# 1_PWR.net
KiCad netlist of a schematic drawn in Altium Designer
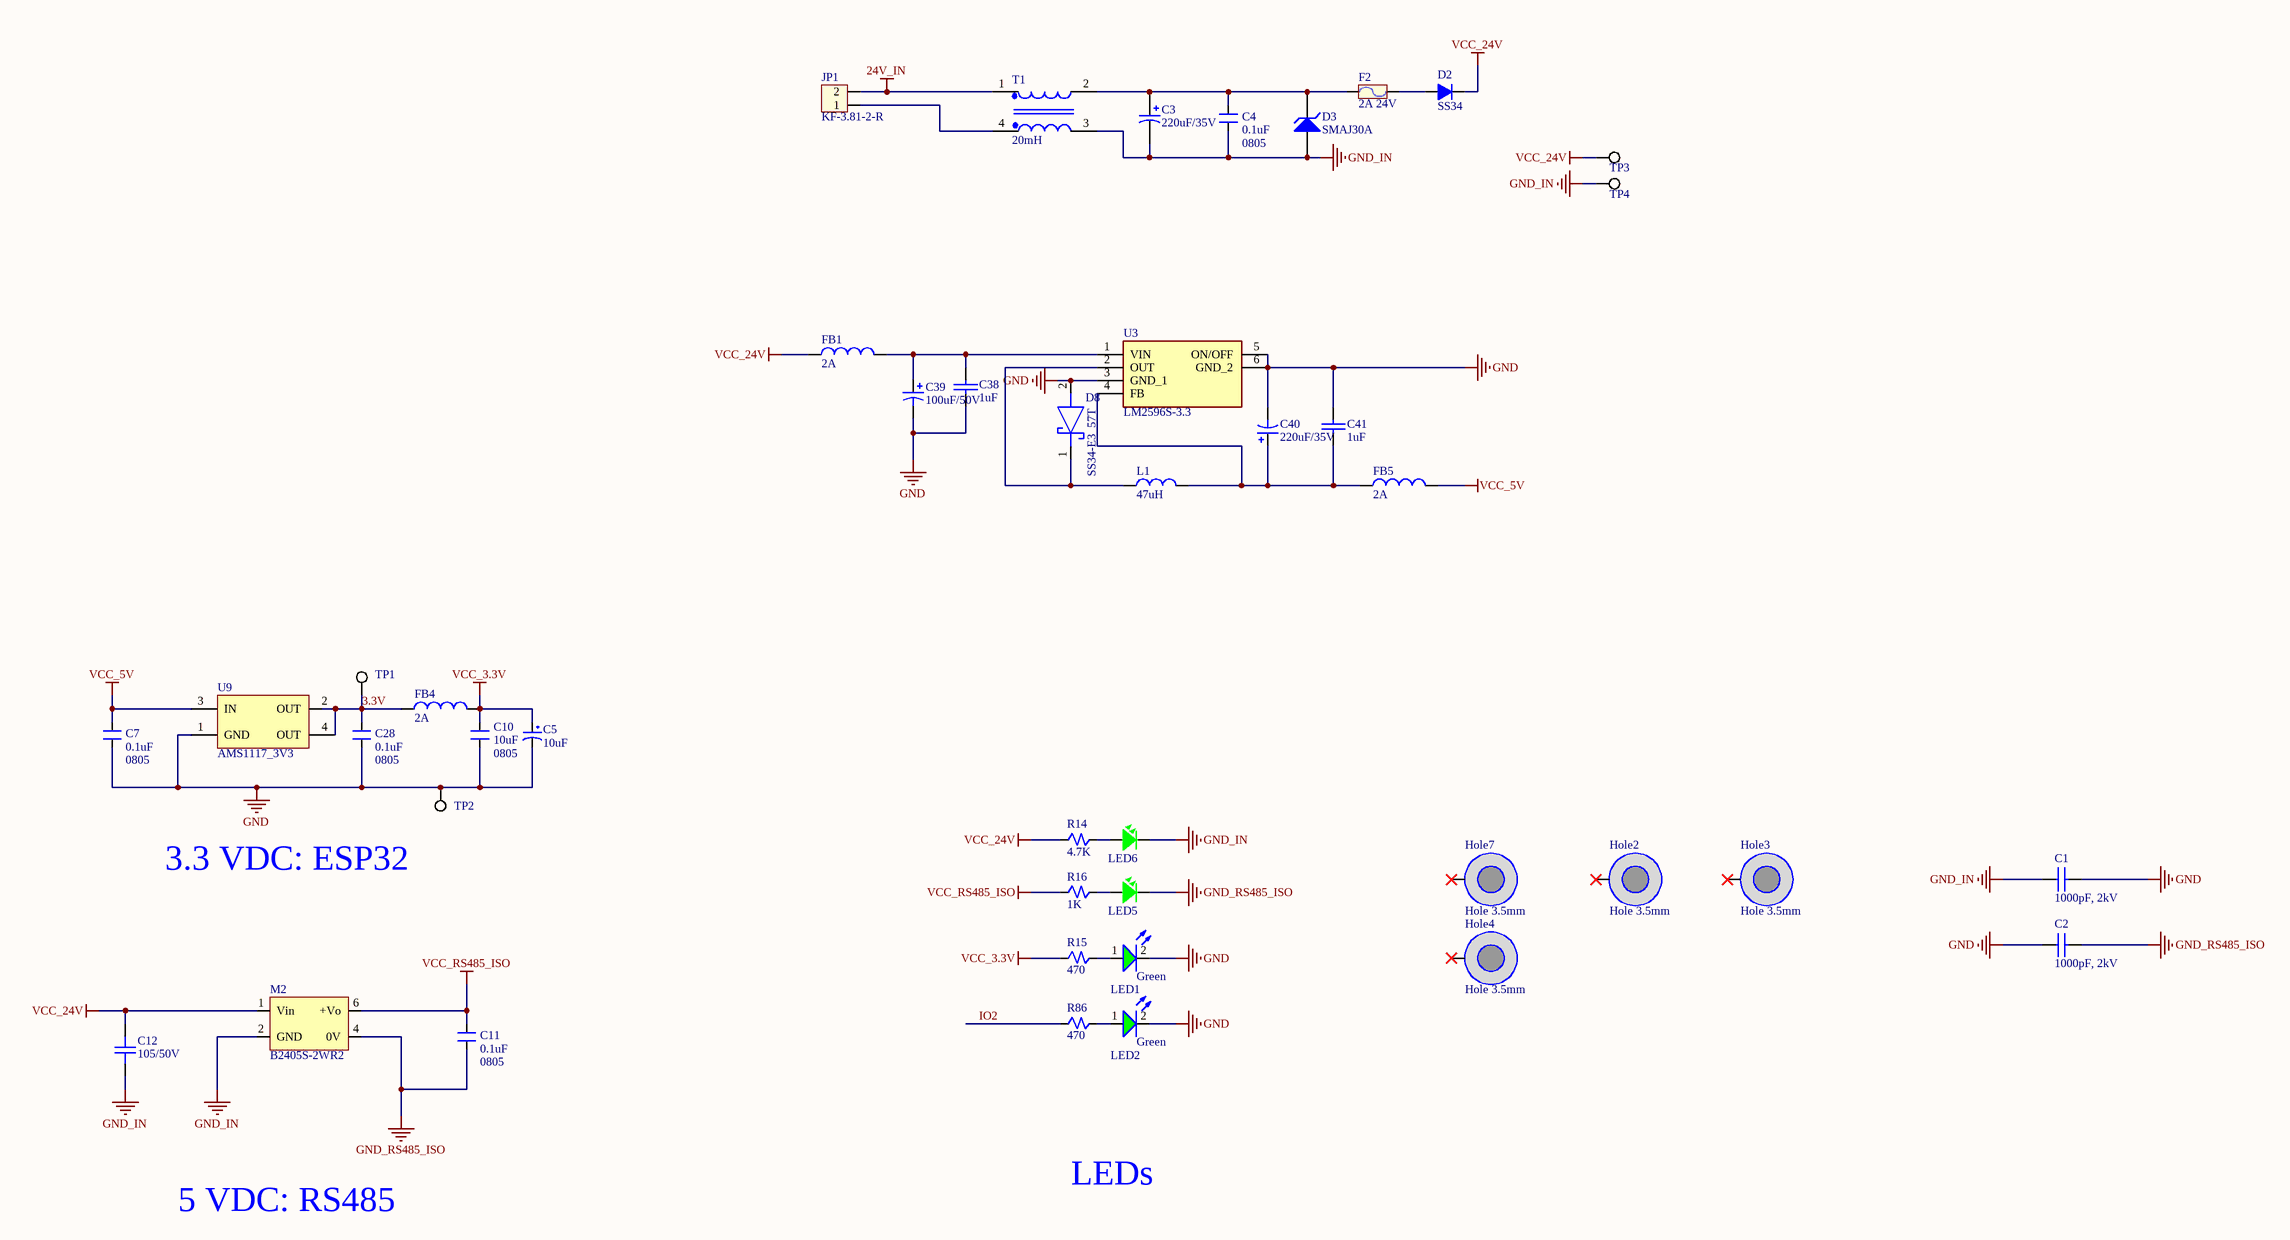
[diagram p0: [1] PWR.SchDoc]

(export (version "E")
  (design (tool "Eeschema 10.0.6"))
  (components
    (comp (ref "C1")
      (value "1000pF, 2kV")
      (footprint "C1206")
      (description "CAP CER 1000PF 2000V X7R 1206 FT")
      (fields (field (name "MANUFACTURER") "Kemet") (field (name "PART NUMBER") "C1206X102KGRACTU"))
      (libsource (lib "DIEN TU HELLO") (part "C1206X102KGRACTU"))
    )
    (comp (ref "C2")
      (value "1000pF, 2kV")
      (footprint "C1206")
      (description "CAP CER 1000PF 2000V X7R 1206 FT")
      (fields (field (name "MANUFACTURER") "Kemet") (field (name "PART NUMBER") "C1206X102KGRACTU"))
      (libsource (lib "DIEN TU HELLO") (part "C1206X102KGRACTU"))
    )
    (comp (ref "C3")
      (value "220uF/35V")
      (footprint "CAP_ALUM_SMD_80102_TYPE_F")
      (description "CAP ALUM 220uF 20% 35V SMD")
      (fields (field (name "PART NUMBER") "EEE-FK1V221P") (field (name "MANUFACTURER") "Panasonic"))
      (libsource (lib "DIEN TU HELLO") (part "EEE-FK1V221P"))
    )
    (comp (ref "C4")
      (value "0.1uF")
      (footprint "CN-SMD-0805")
      (description "CAP CER 0.1UF 50V 0805")
      (fields (field (name "PACKAGE") "0805") (field (name "TOLERANCE") "10%") (field (name "VOLTAGE") "50V"))
      (libsource (lib "DIEN TU HELLO") (part "CAP 0.1uF 0805 10% 50V"))
    )
    (comp (ref "C5")
      (value "10uF")
      (footprint "tu tantalum smd3528")
      (description "Dán")
      (libsource (lib "DIEN TU HELLO") (part "Tu tantalum 10uF 16V SMD3528"))
    )
    (comp (ref "C7")
      (value "0.1uF")
      (footprint "CN-SMD-0805")
      (description "CAP CER 0.1UF 50V 0805")
      (fields (field (name "PACKAGE") "0805") (field (name "TOLERANCE") "10%") (field (name "VOLTAGE") "50V"))
      (libsource (lib "DIEN TU HELLO") (part "CAP 0.1uF 0805 10% 50V"))
    )
    (comp (ref "C10")
      (value "10uF")
      (footprint "CN-SMD-0805")
      (description "CAP CER 10UF 16V 0805")
      (fields
        (field (name "PACKAGE") "0805")
        (field (name "TOLERANCE") "10%")
        (field (name "MANUFACTURER") "Minh Hà")
      )
      (libsource (lib "DIEN TU HELLO") (part "CAP 10uF 0805 10% 16V"))
    )
    (comp (ref "C11")
      (value "0.1uF")
      (footprint "CN-SMD-0805")
      (description "CAP CER 0.1UF 50V 0805")
      (fields (field (name "PACKAGE") "0805") (field (name "TOLERANCE") "10%") (field (name "VOLTAGE") "50V"))
      (libsource (lib "DIEN TU HELLO") (part "CAP 0.1uF 0805 10% 50V"))
    )
    (comp (ref "C12")
      (value "105/50V")
      (footprint "CAPC-1210 (3225)")
      (description "CAP CER 1UF 50V X7R 1210")
      (fields (field (name "PART NUMBER") "CC1210KKX7R9BB105") (field (name "MANUFACTURER") "Yageo"))
      (libsource (lib "DIEN TU HELLO") (part "CC1210KKX7R9BB105"))
    )
    (comp (ref "C28")
      (value "0.1uF")
      (footprint "CN-SMD-0805")
      (description "CAP CER 0.1UF 50V 0805")
      (fields (field (name "PACKAGE") "0805") (field (name "TOLERANCE") "10%") (field (name "VOLTAGE") "50V"))
      (libsource (lib "DIEN TU HELLO") (part "CAP 0.1uF 0805 10% 50V"))
    )
    (comp (ref "C38")
      (value "1uF")
      (footprint "CN-SMD-0805")
      (description "Capacitor")
      (libsource (lib "1942_Device_v2") (part "CAP"))
    )
    (comp (ref "C39")
      (value "100uF/50V")
      (footprint "CAP SMD ALU SIZE F")
      (description "CAP ALUM 100UF 20% 50V RADIAL")
      (fields
        (field (name "MANUFACTURER") "Panasonic Electronic Components")
        (field (name "MANUFACTURER PART NUMBER") "ECA-1HM101B")
      )
      (libsource (lib "Manh_Capacitor") (part "100uF/50V/RADIAL 8X11.5/20%"))
    )
    (comp (ref "C40")
      (value "220uF/35V")
      (footprint "CAP SMD ALU SIZE F")
      (description "CAP ALUM 270UF 20% 35V RADIAL")
      (fields
        (field (name "MANUFACTURER") "Panasonic Electronic Components")
        (field (name "MANUFACTURER PART NUMBER") "EEU-FR1V271LB")
      )
      (libsource (lib "Manh_Capacitor") (part "270uF/35V/RADIAL 8X11.5/20%"))
    )
    (comp (ref "C41")
      (value "1uF")
      (footprint "CN-SMD-0805")
      (description "Capacitor")
      (libsource (lib "1942_Device_v2") (part "CAP"))
    )
    (comp (ref "D2")
      (value "SS34")
      (footprint "diot_smd")
      (description "DIODE SMD S3M 1N5822 3A 40V SMA")
      (fields (field (name "MANUFACTURER") "Minh Hà") (field (name "VOLTAGE") "40V"))
      (libsource (lib "DIEN TU HELLO") (part "SS34_SMA"))
    )
    (comp (ref "D3")
      (value "SMAJ30A")
      (footprint "DIODE_DO214AC_SMA")
      (description "TVS DIODE 30V 48.4V DO214AC")
      (fields (field (name "MANUFACTURER") "Littelfuse Inc"))
      (libsource (lib "DIEN TU HELLO") (part "SMAJ30A"))
    )
    (comp (ref "D8")
      (value "SS34-E3_57T")
      (footprint "diot_smd")
      (description "Schottky Diode")
      (fields
        (field (name "MANUFACTURER_PART_NUMBER") "SS34-E3/57T")
        (field (name "MOUSER PART NUMBER") "625-SS34-E3")
      )
      (libsource (lib "*") (part "SS34-E3_57T"))
    )
    (comp (ref "F2")
      (value "2A 24V")
      (footprint "RES-SMD-1812")
      (description "Cầu Chì Tự Phục Hồi 2A 24V SMD1812")
      (fields (field (name "MANUFACTURER") "Minh Hà") (field (name "PART NUMBER") "MH010033"))
      (libsource (lib "DIEN TU HELLO") (part "FUSE 2A 24V"))
    )
    (comp (ref "FB1")
      (value "2A")
      (footprint "INDC0805")
      (description "FERRITE BEAD 100 mOhm DCR 2A 120 OHM 0805")
      (fields
        (field (name "MANUFACTURER") "Fenghua Electronics")
        (field (name "PART NUMBER") "CBW201209U121T")
      )
      (libsource (lib "DIEN TU HELLO") (part "FERRITE BEAD_CBW201209U121T"))
    )
    (comp (ref "FB4")
      (value "2A")
      (footprint "INDC0805")
      (description "FERRITE BEAD 100 mOhm DCR 2A 120 OHM 0805")
      (fields
        (field (name "MANUFACTURER") "Fenghua Electronics")
        (field (name "PART NUMBER") "CBW201209U121T")
      )
      (libsource (lib "DIEN TU HELLO") (part "FERRITE BEAD_CBW201209U121T"))
    )
    (comp (ref "FB5")
      (value "2A")
      (footprint "INDC0805")
      (description "FERRITE BEAD 100 mOhm DCR 2A 120 OHM 0805")
      (fields
        (field (name "MANUFACTURER") "Fenghua Electronics")
        (field (name "PART NUMBER") "CBW201209U121T")
      )
      (libsource (lib "DIEN TU HELLO") (part "FERRITE BEAD_CBW201209U121T"))
    )
    (comp (ref "Hole2")
      (value "Hole 3.5mm")
      (footprint "Screw Hole 3.5mm")
      (description "VIT Hole 3.5mm")
      (fields (field (name "PART NUMBER") "VIT 3.5mm") (field (name "MANUFACTURER") "Temas"))
      (libsource (lib "DIEN TU HELLO") (part "Hole 3.5mm"))
    )
    (comp (ref "Hole3")
      (value "Hole 3.5mm")
      (footprint "Screw Hole 3.5mm")
      (description "VIT Hole 3.5mm")
      (fields (field (name "PART NUMBER") "VIT 3.5mm") (field (name "MANUFACTURER") "Temas"))
      (libsource (lib "DIEN TU HELLO") (part "Hole 3.5mm"))
    )
    (comp (ref "Hole4")
      (value "Hole 3.5mm")
      (footprint "Screw Hole 3.5mm")
      (description "VIT Hole 3.5mm")
      (fields (field (name "PART NUMBER") "VIT 3.5mm") (field (name "MANUFACTURER") "Temas"))
      (libsource (lib "DIEN TU HELLO") (part "Hole 3.5mm"))
    )
    (comp (ref "Hole7")
      (value "Hole 3.5mm")
      (footprint "Screw Hole 3.5mm")
      (description "VIT Hole 3.5mm")
      (fields (field (name "PART NUMBER") "VIT 3.5mm") (field (name "MANUFACTURER") "Temas"))
      (libsource (lib "DIEN TU HELLO") (part "Hole 3.5mm"))
    )
    (comp (ref "JP1")
      (value "KF-3.81-2-R")
      (footprint "KF-3.81-2-R")
      (description "Terminal Block Plug-in Hàn PCB Chân Cong 3.81mm")
      (libsource (lib "DIEN TU HELLO") (part "Con_2C"))
    )
    (comp (ref "L1")
      (value "47uH")
      (footprint "XL")
      (description "Inductor")
      (libsource (lib "Schlib") (part "Inductor"))
    )
    (comp (ref "LED1")
      (value "Green")
      (footprint "LED5G")
      (description "LED Green 5mm")
      (fields (field (name "Comment") "LED_G_5"))
      (libsource (lib "DIEN TU HELLO") (part "LED_GREEN_5MM"))
    )
    (comp (ref "LED2")
      (value "Green")
      (footprint "LED5G")
      (description "LED Green 5mm")
      (fields (field (name "Comment") "LED_G_5"))
      (libsource (lib "DIEN TU HELLO") (part "LED_GREEN_5MM"))
    )
    (comp (ref "LED5")
      (value "0805 Green")
      (footprint "LED-0805-Blue")
      (description "LED 0805 Màu Xanh Lá (Green)")
      (fields (field (name "MANUFACTURER") "Minh Hà"))
      (libsource (lib "DIEN TU HELLO") (part "LED 0805 Màu Xanh Lá (Green)"))
    )
    (comp (ref "LED6")
      (value "0805 Green")
      (footprint "LED-0805-Blue")
      (description "LED 0805 Màu Xanh Lá (Green)")
      (fields (field (name "MANUFACTURER") "Minh Hà"))
      (libsource (lib "DIEN TU HELLO") (part "LED 0805 Màu Xanh Lá (Green)"))
    )
    (comp (ref "M2")
      (value "B2405S-2WR2")
      (footprint "B_S-2WR2")
      (description "MODULE 24-05V 0.4A Isolated 2W")
      (fields (field (name "MANUFACTURER") "Mornsun"))
      (libsource (lib "DIEN TU HELLO") (part "B2405S-2WR2"))
    )
    (comp (ref "R14")
      (value "4.7K")
      (footprint "RES_0805")
      (description "Điện Trở 4.7 KOhm 0805 1% 1/8W")
      (fields (field (name "PART NUMBER") "Trở 0805 1% 4.7K") (field (name "MANUFACTURER") "Minh Hà"))
      (libsource (lib "DIEN TU HELLO") (part "RES 4.7K 0805 1% 1/8W"))
    )
    (comp (ref "R15")
      (value "470")
      (footprint "RES_0805")
      (description "Điện Trở 470 Ohm 0805 1% 1/8W")
      (fields (field (name "PART NUMBER") "Trở 0805 1% 470R") (field (name "MANUFACTURER") "Minh Hà"))
      (libsource (lib "DIEN TU HELLO") (part "RES 470R 0805 1% 1/8W"))
    )
    (comp (ref "R16")
      (value "1K")
      (footprint "RES_0805")
      (description "Điện Trở 1 KOhm 0805 1% 1/8W")
      (fields (field (name "PART NUMBER") "Trở 0805 1% 1K") (field (name "MANUFACTURER") "Minh Hà"))
      (libsource (lib "DIEN TU HELLO") (part "RES 1K 0805 1% 1/8W"))
    )
    (comp (ref "R86")
      (value "470")
      (footprint "RES_0805")
      (description "Điện Trở 470 Ohm 0805 1% 1/8W")
      (fields (field (name "PART NUMBER") "Trở 0805 1% 470R") (field (name "MANUFACTURER") "Minh Hà"))
      (libsource (lib "DIEN TU HELLO") (part "RES 470R 0805 1% 1/8W"))
    )
    (comp (ref "T1")
      (value "20mH")
      (footprint "UU9.8-10mH")
      (description "Power Transformers 20mH")
      (fields (field (name "MANUFACTURER") "OEM") (field (name "PART NUMBER") "UU9.8-203"))
      (libsource (lib "DIEN TU HELLO") (part "UU9.8-203"))
    )
    (comp (ref "TP1")
      (value "TP 2x2mm")
      (footprint "TP 1.5x1.5mm")
      (description "Test Point 2x2mm")
      (fields (field (name "PART NUMBER") "TEST POINT 2x2MM") (field (name "MANUFACTURER") "TEMAS"))
      (libsource (lib "DIEN TU HELLO") (part "TP 2x2mm"))
    )
    (comp (ref "TP2")
      (value "TP 2x2mm")
      (footprint "TP 1.5x1.5mm")
      (description "Test Point 2x2mm")
      (fields (field (name "PART NUMBER") "TEST POINT 2x2MM") (field (name "MANUFACTURER") "TEMAS"))
      (libsource (lib "DIEN TU HELLO") (part "TP 2x2mm"))
    )
    (comp (ref "TP3")
      (value "TP 2x2mm")
      (footprint "TP 1.5x1.5mm")
      (description "Test Point 2x2mm")
      (fields (field (name "PART NUMBER") "TEST POINT 2x2MM") (field (name "MANUFACTURER") "TEMAS"))
      (libsource (lib "DIEN TU HELLO") (part "TP 2x2mm"))
    )
    (comp (ref "TP4")
      (value "TP 2x2mm")
      (footprint "TP 1.5x1.5mm")
      (description "Test Point 2x2mm")
      (fields (field (name "PART NUMBER") "TEST POINT 2x2MM") (field (name "MANUFACTURER") "TEMAS"))
      (libsource (lib "DIEN TU HELLO") (part "TP 2x2mm"))
    )
    (comp (ref "U3")
      (value "LM2596S-3.3")
      (footprint "TO-263")
      (description "Integrated Circuit")
      (fields (field (name "MOUSER PART NUMBER") "926-LM2596S-33"))
      (libsource (lib "BLE-ESP32") (part "LM2596S-3.3"))
    )
    (comp (ref "U9")
      (value "AMS1117_3V3")
      (footprint "SOT223-4M")
      (description "1A Regulator")
      (libsource (lib "DIEN TU HELLO") (part "AMS1117_3V3"))
    )
  )
  (nets
    (net (code "1") (name "/3.3V") (class "Default")
      (node (ref "C28") (pin "2") (pinfunction "2_2") (pintype "passive"))
      (node (ref "FB4") (pin "1") (pinfunction "1_1") (pintype "passive"))
      (node (ref "TP1") (pin "3") (pinfunction "3_3") (pintype "passive"))
      (node (ref "U9") (pin "2") (pinfunction "OUT_2") (pintype "passive"))
      (node (ref "U9") (pin "4") (pinfunction "OUT_4") (pintype "passive"))
    )
    (net (code "2") (name "/IO2") (class "Default")
      (node (ref "R86") (pin "1") (pinfunction "1_1") (pintype "passive"))
    )
    (net (code "3") (name "24V_IN") (class "Default")
      (node (ref "JP1") (pin "2") (pinfunction "2_2") (pintype "passive"))
      (node (ref "T1") (pin "1") (pinfunction "IN1_1") (pintype "passive"))
    )
    (net (code "4") (name "GND") (class "Default")
      (node (ref "C1") (pin "2") (pinfunction "2_2") (pintype "passive"))
      (node (ref "C10") (pin "1") (pinfunction "1_1") (pintype "passive"))
      (node (ref "C2") (pin "1") (pinfunction "1_1") (pintype "passive"))
      (node (ref "C28") (pin "1") (pinfunction "1_1") (pintype "passive"))
      (node (ref "C38") (pin "2") (pinfunction "2_2") (pintype "passive"))
      (node (ref "C39") (pin "2") (pinfunction "2_2") (pintype "passive"))
      (node (ref "C40") (pin "2") (pinfunction "2_2") (pintype "passive"))
      (node (ref "C41") (pin "1") (pinfunction "1_1") (pintype "passive"))
      (node (ref "C5") (pin "2") (pinfunction "2_2") (pintype "passive"))
      (node (ref "C7") (pin "1") (pinfunction "1_1") (pintype "passive"))
      (node (ref "D8") (pin "2") (pinfunction "A_2") (pintype "passive"))
      (node (ref "LED1") (pin "2") (pinfunction "K_2") (pintype "passive"))
      (node (ref "LED2") (pin "2") (pinfunction "K_2") (pintype "passive"))
      (node (ref "TP2") (pin "3") (pinfunction "3_3") (pintype "passive"))
      (node (ref "U3") (pin "3") (pinfunction "GND_1_3") (pintype "passive"))
      (node (ref "U3") (pin "5") (pinfunction "ON/OFF_5") (pintype "passive"))
      (node (ref "U3") (pin "6") (pinfunction "GND_2_6") (pintype "passive"))
      (node (ref "U9") (pin "1") (pinfunction "GND_1") (pintype "power_in"))
    )
    (net (code "5") (name "GND_IN") (class "Default")
      (node (ref "C1") (pin "1") (pinfunction "1_1") (pintype "passive"))
      (node (ref "C12") (pin "1") (pinfunction "1_1") (pintype "passive"))
      (node (ref "C3") (pin "2") (pinfunction "2_2") (pintype "passive"))
      (node (ref "C4") (pin "1") (pinfunction "1_1") (pintype "passive"))
      (node (ref "D3") (pin "1") (pinfunction "A_1") (pintype "passive"))
      (node (ref "LED6") (pin "2") (pinfunction "2_2") (pintype "passive"))
      (node (ref "M2") (pin "2") (pinfunction "GND_2") (pintype "passive"))
      (node (ref "T1") (pin "3") (pinfunction "OUT2_3") (pintype "passive"))
      (node (ref "TP4") (pin "3") (pinfunction "3_3") (pintype "passive"))
    )
    (net (code "6") (name "GND_RS485_ISO") (class "Default")
      (node (ref "C11") (pin "1") (pinfunction "1_1") (pintype "passive"))
      (node (ref "C2") (pin "2") (pinfunction "2_2") (pintype "passive"))
      (node (ref "LED5") (pin "2") (pinfunction "2_2") (pintype "passive"))
      (node (ref "M2") (pin "4") (pinfunction "0V_4") (pintype "passive"))
    )
    (net (code "7") (name "Net-(D2-A)") (class "Default")
      (node (ref "D2") (pin "1") (pinfunction "A_1") (pintype "passive"))
      (node (ref "F2") (pin "2") (pinfunction "2_2") (pintype "passive"))
    )
    (net (code "8") (name "Net-(D3-K)") (class "Default")
      (node (ref "C3") (pin "1") (pinfunction "1_1") (pintype "passive"))
      (node (ref "C4") (pin "2") (pinfunction "2_2") (pintype "passive"))
      (node (ref "D3") (pin "2") (pinfunction "K_2") (pintype "passive"))
      (node (ref "F2") (pin "1") (pinfunction "1_1") (pintype "passive"))
      (node (ref "T1") (pin "2") (pinfunction "IN2_2") (pintype "passive"))
    )
    (net (code "9") (name "Net-(D8-K)") (class "Default")
      (node (ref "D8") (pin "1") (pinfunction "K_1") (pintype "passive"))
      (node (ref "L1") (pin "1") (pinfunction "1_1") (pintype "passive"))
      (node (ref "U3") (pin "2") (pinfunction "OUT_2") (pintype "passive"))
    )
    (net (code "10") (name "Net-(LED1-A)") (class "Default")
      (node (ref "LED1") (pin "1") (pinfunction "A_1") (pintype "passive"))
      (node (ref "R15") (pin "2") (pinfunction "2_2") (pintype "passive"))
    )
    (net (code "11") (name "Net-(LED2-A)") (class "Default")
      (node (ref "LED2") (pin "1") (pinfunction "A_1") (pintype "passive"))
      (node (ref "R86") (pin "2") (pinfunction "2_2") (pintype "passive"))
    )
    (net (code "12") (name "Net-(LED5-Pad1)") (class "Default")
      (node (ref "LED5") (pin "1") (pinfunction "1_1") (pintype "passive"))
      (node (ref "R16") (pin "2") (pinfunction "2_2") (pintype "passive"))
    )
    (net (code "13") (name "Net-(LED6-Pad1)") (class "Default")
      (node (ref "LED6") (pin "1") (pinfunction "1_1") (pintype "passive"))
      (node (ref "R14") (pin "2") (pinfunction "2_2") (pintype "passive"))
    )
    (net (code "14") (name "Net-(T1-OUT1)") (class "Default")
      (node (ref "JP1") (pin "1") (pinfunction "1_1") (pintype "passive"))
      (node (ref "T1") (pin "4") (pinfunction "OUT1_4") (pintype "passive"))
    )
    (net (code "15") (name "Net-(U3-FB)") (class "Default")
      (node (ref "C40") (pin "1") (pinfunction "1_1") (pintype "passive"))
      (node (ref "C41") (pin "2") (pinfunction "2_2") (pintype "passive"))
      (node (ref "FB5") (pin "1") (pinfunction "1_1") (pintype "passive"))
      (node (ref "L1") (pin "2") (pinfunction "2_2") (pintype "passive"))
      (node (ref "U3") (pin "4") (pinfunction "FB_4") (pintype "passive"))
    )
    (net (code "16") (name "Net-(U3-VIN)") (class "Default")
      (node (ref "C38") (pin "1") (pinfunction "1_1") (pintype "passive"))
      (node (ref "C39") (pin "1") (pinfunction "1_1") (pintype "passive"))
      (node (ref "FB1") (pin "2") (pinfunction "2_2") (pintype "passive"))
      (node (ref "U3") (pin "1") (pinfunction "VIN_1") (pintype "passive"))
    )
    (net (code "17") (name "VCC_3.3V") (class "Default")
      (node (ref "C10") (pin "2") (pinfunction "2_2") (pintype "passive"))
      (node (ref "C5") (pin "1") (pinfunction "1_1") (pintype "passive"))
      (node (ref "FB4") (pin "2") (pinfunction "2_2") (pintype "passive"))
      (node (ref "R15") (pin "1") (pinfunction "1_1") (pintype "passive"))
    )
    (net (code "18") (name "VCC_5V") (class "Default")
      (node (ref "C7") (pin "2") (pinfunction "2_2") (pintype "passive"))
      (node (ref "FB5") (pin "2") (pinfunction "2_2") (pintype "passive"))
      (node (ref "U9") (pin "3") (pinfunction "IN_3") (pintype "power_in"))
    )
    (net (code "19") (name "VCC_24V") (class "Default")
      (node (ref "C12") (pin "2") (pinfunction "2_2") (pintype "passive"))
      (node (ref "D2") (pin "2") (pinfunction "K_2") (pintype "passive"))
      (node (ref "FB1") (pin "1") (pinfunction "1_1") (pintype "passive"))
      (node (ref "M2") (pin "1") (pinfunction "Vin_1") (pintype "passive"))
      (node (ref "R14") (pin "1") (pinfunction "1_1") (pintype "passive"))
      (node (ref "TP3") (pin "3") (pinfunction "3_3") (pintype "passive"))
    )
    (net (code "20") (name "VCC_RS485_ISO") (class "Default")
      (node (ref "C11") (pin "2") (pinfunction "2_2") (pintype "passive"))
      (node (ref "M2") (pin "6") (pinfunction "+Vo_6") (pintype "passive"))
      (node (ref "R16") (pin "1") (pinfunction "1_1") (pintype "passive"))
    )
    (net (code "21") (name "unconnected-(Hole2-hole-Pad1)") (class "Default")
      (node (ref "Hole2") (pin "1") (pinfunction "hole_1") (pintype "passive+no_connect"))
    )
    (net (code "22") (name "unconnected-(Hole3-hole-Pad1)") (class "Default")
      (node (ref "Hole3") (pin "1") (pinfunction "hole_1") (pintype "passive+no_connect"))
    )
    (net (code "23") (name "unconnected-(Hole4-hole-Pad1)") (class "Default")
      (node (ref "Hole4") (pin "1") (pinfunction "hole_1") (pintype "passive+no_connect"))
    )
    (net (code "24") (name "unconnected-(Hole7-hole-Pad1)") (class "Default")
      (node (ref "Hole7") (pin "1") (pinfunction "hole_1") (pintype "passive+no_connect"))
    )
  )
)
